# shiftRegister.net
KiCad netlist of a schematic drawn in Altium Designer
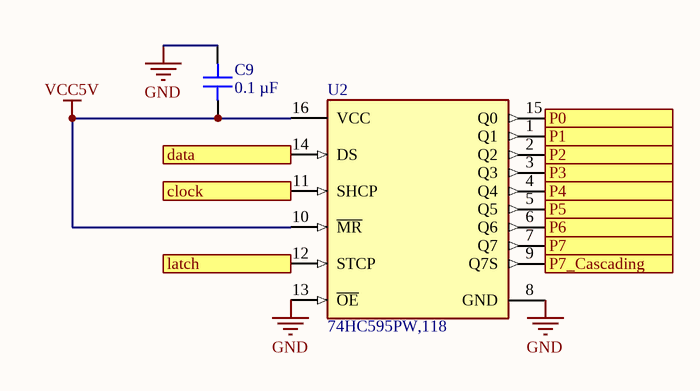
[diagram p0: shiftRegister.SchDoc]

(export (version "E")
  (design (tool "Eeschema 10.0.6"))
  (components
    (comp (ref "C9")
      (value "0.1 µF")
      (footprint "CAP 0603_1608")
      (description "CAP CER 0.1UF 50V X7R 0603")
      (fields (field (name "PART NUMBER") "C0603C104K5RAC7411") (field (name "MANUFACTURER") "KEMET"))
      (libsource (lib "Celestial Altium Library - altium_library") (part "Capacitor"))
    )
    (comp (ref "U2")
      (value "74HC595PW,118")
      (footprint "FP-SOT403-1-MFG")
      (description "IC SHIFT REGISTER 8BIT 16TSSOP")
      (libsource (lib "Altium Content Vault") (part "27683e23285b137cd268a0f18c66bed"))
    )
  )
  (nets
    (net (code "1") (name "/P0") (class "Default")
      (node (ref "U2") (pin "15") (pinfunction "Q0_15") (pintype "output"))
    )
    (net (code "2") (name "/P1") (class "Default")
      (node (ref "U2") (pin "1") (pinfunction "Q1_1") (pintype "output"))
    )
    (net (code "3") (name "/P2") (class "Default")
      (node (ref "U2") (pin "2") (pinfunction "Q2_2") (pintype "output"))
    )
    (net (code "4") (name "/P3") (class "Default")
      (node (ref "U2") (pin "3") (pinfunction "Q3_3") (pintype "output"))
    )
    (net (code "5") (name "/P4") (class "Default")
      (node (ref "U2") (pin "4") (pinfunction "Q4_4") (pintype "output"))
    )
    (net (code "6") (name "/P5") (class "Default")
      (node (ref "U2") (pin "5") (pinfunction "Q5_5") (pintype "output"))
    )
    (net (code "7") (name "/P6") (class "Default")
      (node (ref "U2") (pin "6") (pinfunction "Q6_6") (pintype "output"))
    )
    (net (code "8") (name "/P7") (class "Default")
      (node (ref "U2") (pin "7") (pinfunction "Q7_7") (pintype "output"))
    )
    (net (code "9") (name "/P7_Cascading") (class "Default")
      (node (ref "U2") (pin "9") (pinfunction "Q7S_9") (pintype "output"))
    )
    (net (code "10") (name "/clock") (class "Default")
      (node (ref "U2") (pin "11") (pinfunction "SHCP_11") (pintype "input"))
    )
    (net (code "11") (name "/data") (class "Default")
      (node (ref "U2") (pin "14") (pinfunction "DS_14") (pintype "input"))
    )
    (net (code "12") (name "/latch") (class "Default")
      (node (ref "U2") (pin "12") (pinfunction "STCP_12") (pintype "input"))
    )
    (net (code "13") (name "GND") (class "Default")
      (node (ref "C9") (pin "2") (pinfunction "2_2") (pintype "passive"))
      (node (ref "U2") (pin "13") (pinfunction "~{OE}_13") (pintype "input"))
      (node (ref "U2") (pin "8") (pinfunction "GND_8") (pintype "power_in"))
    )
    (net (code "14") (name "VCC5V") (class "Default")
      (node (ref "C9") (pin "1") (pinfunction "1_1") (pintype "passive"))
      (node (ref "U2") (pin "10") (pinfunction "~{MR}_10") (pintype "input"))
      (node (ref "U2") (pin "16") (pinfunction "VCC_16") (pintype "power_in"))
    )
  )
)
